# Circuit_driver_2.net
KiCad netlist of a schematic drawn in Altium Designer
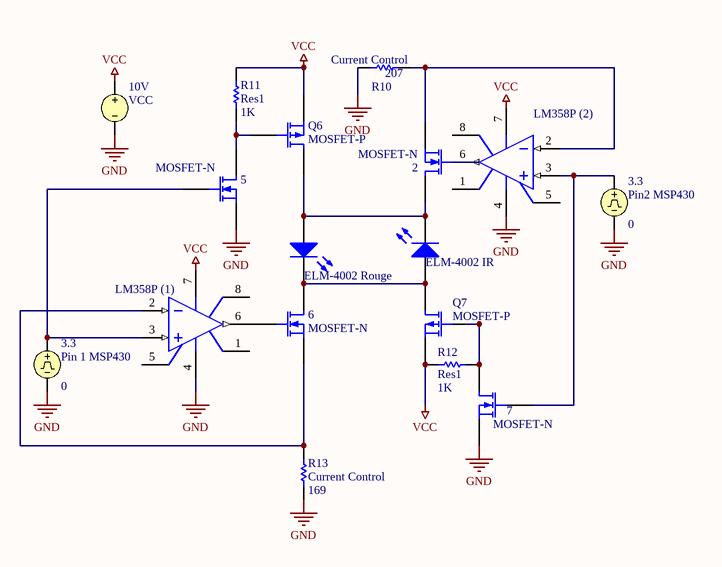
[diagram p0: Circuit_driver_2.SchDoc]

(export (version "E")
  (design (tool "Eeschema 10.0.6"))
  (components
    (comp (ref "2")
      (value "MOSFET-N")
      (footprint "E3")
      (description "N-Channel MOSFET")
      (fields (field (name "PUBLISHER") "Altium Limited"))
      (libsource (lib "Miscellaneous Devices") (part "MOSFET-N"))
    )
    (comp (ref "5")
      (value "MOSFET-N")
      (footprint "E3")
      (description "N-Channel MOSFET")
      (fields (field (name "PUBLISHER") "Altium Limited"))
      (libsource (lib "Miscellaneous Devices") (part "MOSFET-N"))
    )
    (comp (ref "6")
      (value "MOSFET-N")
      (footprint "E3")
      (description "N-Channel MOSFET")
      (fields (field (name "PUBLISHER") "Altium Limited"))
      (libsource (lib "Miscellaneous Devices") (part "MOSFET-N"))
    )
    (comp (ref "7")
      (value "MOSFET-N")
      (footprint "E3")
      (description "N-Channel MOSFET")
      (fields (field (name "PUBLISHER") "Altium Limited"))
      (libsource (lib "Miscellaneous Devices") (part "MOSFET-N"))
    )
    (comp (ref "ELM-4002 IR")
      (value "IR")
      (footprint "LED-1")
      (description "Typical RED GaAs LED")
      (fields (field (name "PUBLISHER") "Altium Limited"))
      (libsource (lib "Miscellaneous Devices") (part "LED1"))
    )
    (comp (ref "ELM-4002 Rouge")
      (value "Rouge")
      (footprint "LED-1")
      (description "Typical RED GaAs LED")
      (fields (field (name "PUBLISHER") "Altium Limited"))
      (libsource (lib "Miscellaneous Devices") (part "LED1"))
    )
    (comp (ref "LM358P (1)")
      (value "Op Amp")
      (footprint "H-08A")
      (description "FET Operational Amplifier")
      (fields (field (name "PUBLISHER") "Altium Limited"))
      (libsource (lib "Miscellaneous Devices") (part "Op Amp"))
    )
    (comp (ref "LM358P (2)")
      (value "Op Amp")
      (footprint "H-08A")
      (description "FET Operational Amplifier")
      (fields (field (name "PUBLISHER") "Altium Limited"))
      (libsource (lib "Miscellaneous Devices") (part "Op Amp"))
    )
    (comp (ref "Pin 1 MSP430")
      (value "~")
      (description "Pulse Voltage Source")
      (fields
        (field (name "INITIAL VALUE") "0")
        (field (name "PULSED VALUE") "3.3")
        (field (name "PUBLISHER") "Altium Limited")
      )
      (libsource (lib "Simulation Sources") (part "VPULSE"))
    )
    (comp (ref "Pin2 MSP430")
      (value "~")
      (description "Pulse Voltage Source")
      (fields
        (field (name "INITIAL VALUE") "0")
        (field (name "PULSED VALUE") "3.3")
        (field (name "PUBLISHER") "Altium Limited")
      )
      (libsource (lib "Simulation Sources") (part "VPULSE"))
    )
    (comp (ref "Q6")
      (value "MOSFET-P")
      (footprint "E3")
      (description "P-Channel MOSFET")
      (fields (field (name "PUBLISHER") "Altium Limited"))
      (libsource (lib "Miscellaneous Devices") (part "MOSFET-P"))
    )
    (comp (ref "Q7")
      (value "MOSFET-P")
      (footprint "E3")
      (description "P-Channel MOSFET")
      (fields (field (name "PUBLISHER") "Altium Limited"))
      (libsource (lib "Miscellaneous Devices") (part "MOSFET-P"))
    )
    (comp (ref "R10")
      (value "Current Control")
      (footprint "AXIAL-0.3")
      (description "Resistor")
      (fields (field (name "ALTIUM_VALUE") "207") (field (name "PUBLISHER") "Altium Limited"))
      (libsource (lib "Miscellaneous Devices") (part "Res1"))
    )
    (comp (ref "R11")
      (value "Res1")
      (footprint "AXIAL-0.3")
      (description "Resistor")
      (fields (field (name "ALTIUM_VALUE") "1K") (field (name "PUBLISHER") "Altium Limited"))
      (libsource (lib "Miscellaneous Devices") (part "Res1"))
    )
    (comp (ref "R12")
      (value "Res1")
      (footprint "AXIAL-0.3")
      (description "Resistor")
      (fields (field (name "ALTIUM_VALUE") "1K") (field (name "PUBLISHER") "Altium Limited"))
      (libsource (lib "Miscellaneous Devices") (part "Res1"))
    )
    (comp (ref "R13")
      (value "Current Control")
      (footprint "AXIAL-0.3")
      (description "Resistor")
      (fields (field (name "ALTIUM_VALUE") "169") (field (name "PUBLISHER") "Altium Limited"))
      (libsource (lib "Miscellaneous Devices") (part "Res1"))
    )
    (comp (ref "VCC")
      (value "10V")
      (description "Voltage Source")
      (fields (field (name "Comment") "VSRC") (field (name "PUBLISHER") "Altium Limited"))
      (libsource (lib "Simulation Sources") (part "VSRC"))
    )
  )
  (nets
    (net (code "1") (name "GND") (class "Default")
      (node (ref "5") (pin "3") (pinfunction "S_3") (pintype "passive"))
      (node (ref "7") (pin "3") (pinfunction "S_3") (pintype "passive"))
      (node (ref "LM358P (1)") (pin "4") (pinfunction "V-_4") (pintype "power_in"))
      (node (ref "LM358P (2)") (pin "4") (pinfunction "V-_4") (pintype "power_in"))
      (node (ref "Pin 1 MSP430") (pin "2") (pinfunction "2_2") (pintype "passive"))
      (node (ref "Pin2 MSP430") (pin "2") (pinfunction "2_2") (pintype "passive"))
      (node (ref "R10") (pin "2") (pinfunction "2_2") (pintype "passive"))
      (node (ref "R13") (pin "1") (pinfunction "1_1") (pintype "passive"))
      (node (ref "VCC") (pin "2") (pinfunction "2_2") (pintype "passive"))
    )
    (net (code "2") (name "Net-(2-D)") (class "Default")
      (node (ref "2") (pin "1") (pinfunction "D_1") (pintype "passive"))
      (node (ref "ELM-4002 IR") (pin "2") (pinfunction "K_2") (pintype "passive"))
      (node (ref "ELM-4002 Rouge") (pin "1") (pinfunction "A_1") (pintype "passive"))
      (node (ref "Q6") (pin "1") (pinfunction "D_1") (pintype "passive"))
    )
    (net (code "3") (name "Net-(2-G)") (class "Default")
      (node (ref "2") (pin "2") (pinfunction "G_2") (pintype "passive"))
      (node (ref "LM358P (2)") (pin "6") (pinfunction "OUT_6") (pintype "output"))
    )
    (net (code "4") (name "Net-(2-S)") (class "Default")
      (node (ref "2") (pin "3") (pinfunction "S_3") (pintype "passive"))
      (node (ref "LM358P (2)") (pin "2") (pinfunction "IN-_2") (pintype "input"))
      (node (ref "R10") (pin "1") (pinfunction "1_1") (pintype "passive"))
    )
    (net (code "5") (name "Net-(5-D)") (class "Default")
      (node (ref "5") (pin "1") (pinfunction "D_1") (pintype "passive"))
      (node (ref "Q6") (pin "2") (pinfunction "G_2") (pintype "passive"))
      (node (ref "R11") (pin "1") (pinfunction "1_1") (pintype "passive"))
    )
    (net (code "6") (name "Net-(5-G)") (class "Default")
      (node (ref "5") (pin "2") (pinfunction "G_2") (pintype "passive"))
      (node (ref "LM358P (1)") (pin "3") (pinfunction "IN+_3") (pintype "input"))
      (node (ref "Pin 1 MSP430") (pin "1") (pinfunction "1_1") (pintype "passive"))
    )
    (net (code "7") (name "Net-(6-D)") (class "Default")
      (node (ref "6") (pin "1") (pinfunction "D_1") (pintype "passive"))
      (node (ref "ELM-4002 IR") (pin "1") (pinfunction "A_1") (pintype "passive"))
      (node (ref "ELM-4002 Rouge") (pin "2") (pinfunction "K_2") (pintype "passive"))
      (node (ref "Q7") (pin "1") (pinfunction "D_1") (pintype "passive"))
    )
    (net (code "8") (name "Net-(6-G)") (class "Default")
      (node (ref "6") (pin "2") (pinfunction "G_2") (pintype "passive"))
      (node (ref "LM358P (1)") (pin "6") (pinfunction "OUT_6") (pintype "output"))
    )
    (net (code "9") (name "Net-(6-S)") (class "Default")
      (node (ref "6") (pin "3") (pinfunction "S_3") (pintype "passive"))
      (node (ref "LM358P (1)") (pin "2") (pinfunction "IN-_2") (pintype "input"))
      (node (ref "R13") (pin "2") (pinfunction "2_2") (pintype "passive"))
    )
    (net (code "10") (name "Net-(7-D)") (class "Default")
      (node (ref "7") (pin "1") (pinfunction "D_1") (pintype "passive"))
      (node (ref "Q7") (pin "2") (pinfunction "G_2") (pintype "passive"))
      (node (ref "R12") (pin "1") (pinfunction "1_1") (pintype "passive"))
    )
    (net (code "11") (name "Net-(7-G)") (class "Default")
      (node (ref "7") (pin "2") (pinfunction "G_2") (pintype "passive"))
      (node (ref "LM358P (2)") (pin "3") (pinfunction "IN+_3") (pintype "input"))
      (node (ref "Pin2 MSP430") (pin "1") (pinfunction "1_1") (pintype "passive"))
    )
    (net (code "12") (name "VCC") (class "Default")
      (node (ref "LM358P (1)") (pin "7") (pinfunction "V+_7") (pintype "power_in"))
      (node (ref "LM358P (2)") (pin "7") (pinfunction "V+_7") (pintype "power_in"))
      (node (ref "Q6") (pin "3") (pinfunction "S_3") (pintype "passive"))
      (node (ref "Q7") (pin "3") (pinfunction "S_3") (pintype "passive"))
      (node (ref "R11") (pin "2") (pinfunction "2_2") (pintype "passive"))
      (node (ref "R12") (pin "2") (pinfunction "2_2") (pintype "passive"))
      (node (ref "VCC") (pin "1") (pinfunction "1_1") (pintype "passive"))
    )
    (net (code "13") (name "unconnected-(LM358P (1)-OS_NUL-Pad1)") (class "Default")
      (node (ref "LM358P (1)") (pin "1") (pinfunction "OS_NUL_1") (pintype "passive"))
    )
    (net (code "14") (name "unconnected-(LM358P (1)-OS_NUL-Pad5)") (class "Default")
      (node (ref "LM358P (1)") (pin "5") (pinfunction "OS_NUL_5") (pintype "passive"))
    )
    (net (code "15") (name "unconnected-(LM358P (1)-TAB-Pad8)") (class "Default")
      (node (ref "LM358P (1)") (pin "8") (pinfunction "TAB_8") (pintype "passive"))
    )
    (net (code "16") (name "unconnected-(LM358P (2)-OS_NUL-Pad1)") (class "Default")
      (node (ref "LM358P (2)") (pin "1") (pinfunction "OS_NUL_1") (pintype "passive"))
    )
    (net (code "17") (name "unconnected-(LM358P (2)-OS_NUL-Pad5)") (class "Default")
      (node (ref "LM358P (2)") (pin "5") (pinfunction "OS_NUL_5") (pintype "passive"))
    )
    (net (code "18") (name "unconnected-(LM358P (2)-TAB-Pad8)") (class "Default")
      (node (ref "LM358P (2)") (pin "8") (pinfunction "TAB_8") (pintype "passive"))
    )
  )
)
